# PewCB_Blank3x3.net
KiCad netlist of a schematic drawn in Altium Designer
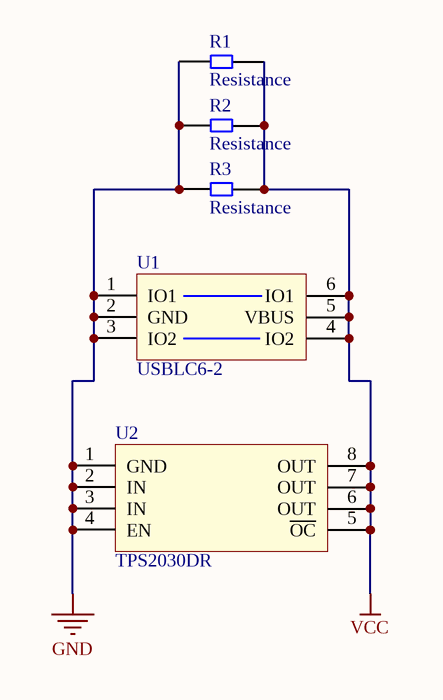
[diagram p0: PewCB.Blank3x3.SchDoc]

(export (version "E")
  (design (tool "Eeschema 10.0.6"))
  (components
    (comp (ref "R1")
      (value "Resistance")
      (footprint "RES_0805")
      (libsource (lib "PassiveComponents") (part "Resistor"))
    )
    (comp (ref "R2")
      (value "Resistance")
      (footprint "RES_0805")
      (libsource (lib "PassiveComponents") (part "Resistor"))
    )
    (comp (ref "R3")
      (value "Resistance")
      (footprint "RES_0805")
      (libsource (lib "PassiveComponents") (part "Resistor"))
    )
    (comp (ref "U1")
      (value "USBLC6-2")
      (footprint "SOT23-6")
      (description "USB ESD PROTECTION")
      (libsource (lib "PowerManagement") (part "USBLC6-2"))
    )
    (comp (ref "U2")
      (value "TPS2030DR")
      (footprint "SO8")
      (description "Power Switch/Driver 1:1 N-Channel 200mA 8-SOIC")
      (libsource (lib "PowerManagement") (part "TPS2030DR"))
    )
  )
  (nets
    (net (code "1") (name "GND") (class "Default")
      (node (ref "R1") (pin "1") (pinfunction "1_1") (pintype "passive"))
      (node (ref "R2") (pin "1") (pinfunction "1_1") (pintype "passive"))
      (node (ref "R3") (pin "1") (pinfunction "1_1") (pintype "passive"))
      (node (ref "U1") (pin "1") (pinfunction "IO1_1") (pintype "passive"))
      (node (ref "U1") (pin "2") (pinfunction "GND_2") (pintype "passive"))
      (node (ref "U1") (pin "3") (pinfunction "IO2_3") (pintype "passive"))
      (node (ref "U2") (pin "1") (pinfunction "GND_1") (pintype "power_in"))
      (node (ref "U2") (pin "2") (pinfunction "IN_2") (pintype "power_in"))
      (node (ref "U2") (pin "3") (pinfunction "IN_3") (pintype "power_in"))
      (node (ref "U2") (pin "4") (pinfunction "EN_4") (pintype "passive"))
    )
    (net (code "2") (name "VCC") (class "Default")
      (node (ref "R1") (pin "2") (pinfunction "2_2") (pintype "passive"))
      (node (ref "R2") (pin "2") (pinfunction "2_2") (pintype "passive"))
      (node (ref "R3") (pin "2") (pinfunction "2_2") (pintype "passive"))
      (node (ref "U1") (pin "4") (pinfunction "IO2_4") (pintype "passive"))
      (node (ref "U1") (pin "5") (pinfunction "VBUS_5") (pintype "passive"))
      (node (ref "U1") (pin "6") (pinfunction "IO1_6") (pintype "passive"))
      (node (ref "U2") (pin "5") (pinfunction "~{OC}_5") (pintype "passive"))
      (node (ref "U2") (pin "6") (pinfunction "OUT_6") (pintype "passive"))
      (node (ref "U2") (pin "7") (pinfunction "OUT_7") (pintype "passive"))
      (node (ref "U2") (pin "8") (pinfunction "OUT_8") (pintype "passive"))
    )
  )
)
